# afron_atmega328_chassis_B.net
KiCad netlist of a schematic drawn in EAGLE
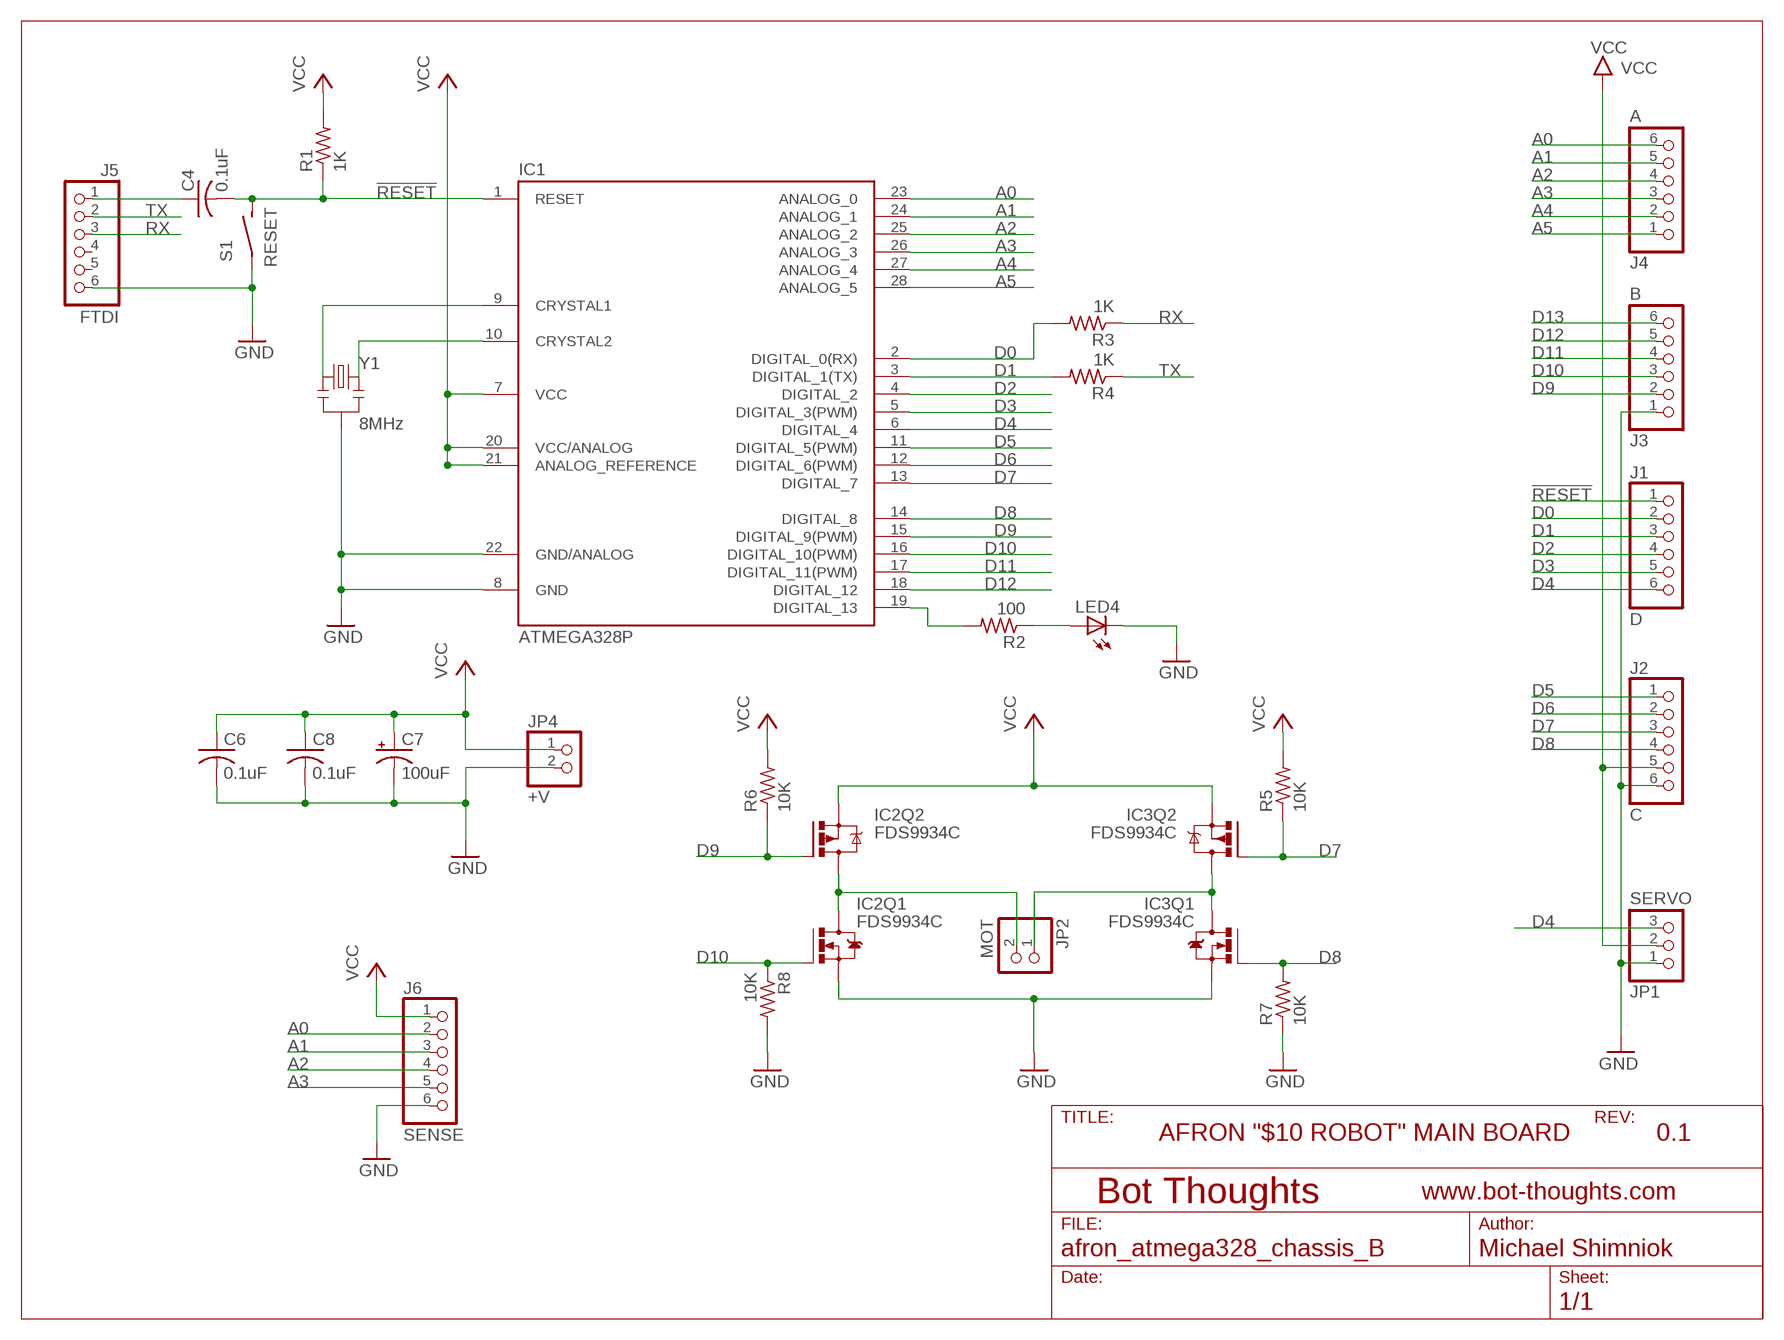
[diagram p0: schematic, sheet 1]

(export (version "E")
  (design (tool "Eeschema 10.0.6"))
  (components
    (comp (ref "C4")
      (value "0.1uF")
      (footprint "eagle-import:C050-024X044")
      (libsource (lib "eagle-import") (part "C-US050-024X044"))
    )
    (comp (ref "C6")
      (value "0.1uF")
      (footprint "eagle-import:C050-024X044")
      (libsource (lib "eagle-import") (part "C-US050-024X044"))
    )
    (comp (ref "C7")
      (value "100uF")
      (footprint "eagle-import:E2,5-6")
      (libsource (lib "eagle-import") (part "CPOL-USE2.5-6"))
    )
    (comp (ref "C8")
      (value "0.1uF")
      (footprint "eagle-import:C050-024X044")
      (libsource (lib "eagle-import") (part "C-US050-024X044"))
    )
    (comp (ref "IC1")
      (value "ATMEGA328P")
      (footprint "eagle-import:DIL28-3")
      (libsource (lib "eagle-import") (part "ATMEGA168-PU"))
    )
    (comp (ref "IC2")
      (value "FDS9934C")
      (footprint "eagle-import:SOIC8")
      (libsource (lib "eagle-import") (part "FDS9934C"))
    )
    (comp (ref "IC3")
      (value "FDS9934C")
      (footprint "eagle-import:SOIC8")
      (libsource (lib "eagle-import") (part "FDS9934C"))
    )
    (comp (ref "J1")
      (value "D")
      (footprint "eagle-import:1X06")
      (libsource (lib "eagle-import") (part "PINHD-1X06_2.54"))
    )
    (comp (ref "J2")
      (value "C")
      (footprint "eagle-import:1X06")
      (libsource (lib "eagle-import") (part "PINHD-1X06_2.54"))
    )
    (comp (ref "J3")
      (value "B")
      (footprint "eagle-import:1X06")
      (libsource (lib "eagle-import") (part "PINHD-1X06_2.54"))
    )
    (comp (ref "J4")
      (value "A")
      (footprint "eagle-import:1X06")
      (libsource (lib "eagle-import") (part "PINHD-1X06_2.54"))
    )
    (comp (ref "J5")
      (value "FTDI")
      (footprint "eagle-import:1X06")
      (libsource (lib "eagle-import") (part "PINHD-1X06_2.54"))
    )
    (comp (ref "J6")
      (value "SENSE")
      (footprint "eagle-import:1X06")
      (libsource (lib "eagle-import") (part "PINHD-1X06_2.54"))
    )
    (comp (ref "JP1")
      (value "SERVO")
      (footprint "eagle-import:1X03")
      (libsource (lib "eagle-import") (part "PINHD-1X03_2.54"))
    )
    (comp (ref "JP2")
      (value "MOT")
      (footprint "eagle-import:1X02-S")
      (libsource (lib "eagle-import") (part "PINHD-1X02_2.54-S"))
    )
    (comp (ref "JP4")
      (value "+V")
      (footprint "eagle-import:1X02-S")
      (libsource (lib "eagle-import") (part "PINHD-1X02_2.54-S"))
    )
    (comp (ref "LED4")
      (value "LED3MM")
      (footprint "eagle-import:LED3MM")
      (libsource (lib "eagle-import") (part "LED3MM"))
    )
    (comp (ref "R1")
      (value "1K")
      (footprint "eagle-import:0204_5")
      (libsource (lib "eagle-import") (part "R-US_0204/5"))
    )
    (comp (ref "R2")
      (value "100")
      (footprint "eagle-import:0204_5")
      (libsource (lib "eagle-import") (part "R-US_0204/5"))
    )
    (comp (ref "R3")
      (value "1K")
      (footprint "eagle-import:0204_5")
      (libsource (lib "eagle-import") (part "R-US_0204/5"))
    )
    (comp (ref "R4")
      (value "1K")
      (footprint "eagle-import:0204_5")
      (libsource (lib "eagle-import") (part "R-US_0204/5"))
    )
    (comp (ref "R5")
      (value "10K")
      (footprint "eagle-import:0204_5")
      (libsource (lib "eagle-import") (part "R-US_0204/5"))
    )
    (comp (ref "R6")
      (value "10K")
      (footprint "eagle-import:0204_5")
      (libsource (lib "eagle-import") (part "R-US_0204/5"))
    )
    (comp (ref "R7")
      (value "10K")
      (footprint "eagle-import:0204_5")
      (libsource (lib "eagle-import") (part "R-US_0204/5"))
    )
    (comp (ref "R8")
      (value "10K")
      (footprint "eagle-import:0204_5")
      (libsource (lib "eagle-import") (part "R-US_0204/5"))
    )
    (comp (ref "S1")
      (value "RESET")
      (footprint "eagle-import:6MMTACTILE")
      (libsource (lib "eagle-import") (part "SPST_TACT2"))
    )
    (comp (ref "Y1")
      (value "8MHz")
      (footprint "eagle-import:RESONATOR-PTH")
      (libsource (lib "eagle-import") (part "RESONATORPTH"))
    )
  )
  (nets
    (net (code "1") (name "/A0") (class "Default")
      (node (ref "IC1") (pin "23") (pinfunction "ANALOG_0_23") (pintype "bidirectional"))
      (node (ref "J4") (pin "6") (pinfunction "6_6") (pintype "passive"))
      (node (ref "J6") (pin "2") (pinfunction "2_2") (pintype "passive"))
    )
    (net (code "2") (name "/A1") (class "Default")
      (node (ref "IC1") (pin "24") (pinfunction "ANALOG_1_24") (pintype "bidirectional"))
      (node (ref "J4") (pin "5") (pinfunction "5_5") (pintype "passive"))
      (node (ref "J6") (pin "3") (pinfunction "3_3") (pintype "passive"))
    )
    (net (code "3") (name "/A2") (class "Default")
      (node (ref "IC1") (pin "25") (pinfunction "ANALOG_2_25") (pintype "bidirectional"))
      (node (ref "J4") (pin "4") (pinfunction "4_4") (pintype "passive"))
      (node (ref "J6") (pin "4") (pinfunction "4_4") (pintype "passive"))
    )
    (net (code "4") (name "/A3") (class "Default")
      (node (ref "IC1") (pin "26") (pinfunction "ANALOG_3_26") (pintype "bidirectional"))
      (node (ref "J4") (pin "3") (pinfunction "3_3") (pintype "passive"))
      (node (ref "J6") (pin "5") (pinfunction "5_5") (pintype "passive"))
    )
    (net (code "5") (name "/A4") (class "Default")
      (node (ref "IC1") (pin "27") (pinfunction "ANALOG_4_27") (pintype "bidirectional"))
      (node (ref "J4") (pin "2") (pinfunction "2_2") (pintype "passive"))
    )
    (net (code "6") (name "/A5") (class "Default")
      (node (ref "IC1") (pin "28") (pinfunction "ANALOG_5_28") (pintype "bidirectional"))
      (node (ref "J4") (pin "1") (pinfunction "1_1") (pintype "passive"))
    )
    (net (code "7") (name "/D0") (class "Default")
      (node (ref "IC1") (pin "2") (pinfunction "DIGITAL_0(RX)_2") (pintype "bidirectional"))
      (node (ref "J1") (pin "2") (pinfunction "2_2") (pintype "passive"))
      (node (ref "R3") (pin "2") (pinfunction "2_2") (pintype "passive"))
    )
    (net (code "8") (name "/D1") (class "Default")
      (node (ref "IC1") (pin "3") (pinfunction "DIGITAL_1(TX)_3") (pintype "bidirectional"))
      (node (ref "J1") (pin "3") (pinfunction "3_3") (pintype "passive"))
      (node (ref "R4") (pin "2") (pinfunction "2_2") (pintype "passive"))
    )
    (net (code "9") (name "/D2") (class "Default")
      (node (ref "IC1") (pin "4") (pinfunction "DIGITAL_2_4") (pintype "bidirectional"))
      (node (ref "J1") (pin "4") (pinfunction "4_4") (pintype "passive"))
    )
    (net (code "10") (name "/D3") (class "Default")
      (node (ref "IC1") (pin "5") (pinfunction "DIGITAL_3(PWM)_5") (pintype "bidirectional"))
      (node (ref "J1") (pin "5") (pinfunction "5_5") (pintype "passive"))
    )
    (net (code "11") (name "/D4") (class "Default")
      (node (ref "IC1") (pin "6") (pinfunction "DIGITAL_4_6") (pintype "bidirectional"))
      (node (ref "J1") (pin "6") (pinfunction "6_6") (pintype "passive"))
      (node (ref "JP1") (pin "3") (pinfunction "3_3") (pintype "passive"))
    )
    (net (code "12") (name "/D5") (class "Default")
      (node (ref "IC1") (pin "11") (pinfunction "DIGITAL_5(PWM)_11") (pintype "bidirectional"))
      (node (ref "J2") (pin "1") (pinfunction "1_1") (pintype "passive"))
    )
    (net (code "13") (name "/D6") (class "Default")
      (node (ref "IC1") (pin "12") (pinfunction "DIGITAL_6(PWM)_12") (pintype "bidirectional"))
      (node (ref "J2") (pin "2") (pinfunction "2_2") (pintype "passive"))
    )
    (net (code "14") (name "/D7") (class "Default")
      (node (ref "IC1") (pin "13") (pinfunction "DIGITAL_7_13") (pintype "bidirectional"))
      (node (ref "IC3") (pin "4") (pinfunction "G_4") (pintype "passive"))
      (node (ref "J2") (pin "3") (pinfunction "3_3") (pintype "passive"))
      (node (ref "R5") (pin "1") (pinfunction "1_1") (pintype "passive"))
    )
    (net (code "15") (name "/D8") (class "Default")
      (node (ref "IC1") (pin "14") (pinfunction "DIGITAL_8_14") (pintype "bidirectional"))
      (node (ref "IC3") (pin "2") (pinfunction "G_2") (pintype "passive"))
      (node (ref "J2") (pin "4") (pinfunction "4_4") (pintype "passive"))
      (node (ref "R7") (pin "2") (pinfunction "2_2") (pintype "passive"))
    )
    (net (code "16") (name "/D9") (class "Default")
      (node (ref "IC1") (pin "15") (pinfunction "DIGITAL_9(PWM)_15") (pintype "bidirectional"))
      (node (ref "IC2") (pin "4") (pinfunction "G_4") (pintype "passive"))
      (node (ref "J3") (pin "2") (pinfunction "2_2") (pintype "passive"))
      (node (ref "R6") (pin "1") (pinfunction "1_1") (pintype "passive"))
    )
    (net (code "17") (name "/D10") (class "Default")
      (node (ref "IC1") (pin "16") (pinfunction "DIGITAL_10(PWM)_16") (pintype "bidirectional"))
      (node (ref "IC2") (pin "2") (pinfunction "G_2") (pintype "passive"))
      (node (ref "J3") (pin "3") (pinfunction "3_3") (pintype "passive"))
      (node (ref "R8") (pin "1") (pinfunction "1_1") (pintype "passive"))
    )
    (net (code "18") (name "/D11") (class "Default")
      (node (ref "IC1") (pin "17") (pinfunction "DIGITAL_11(PWM)_17") (pintype "bidirectional"))
      (node (ref "J3") (pin "4") (pinfunction "4_4") (pintype "passive"))
    )
    (net (code "19") (name "/D12") (class "Default")
      (node (ref "IC1") (pin "18") (pinfunction "DIGITAL_12_18") (pintype "bidirectional"))
      (node (ref "J3") (pin "5") (pinfunction "5_5") (pintype "passive"))
    )
    (net (code "20") (name "/D13") (class "Default")
      (node (ref "IC1") (pin "19") (pinfunction "DIGITAL_13_19") (pintype "bidirectional"))
      (node (ref "J3") (pin "6") (pinfunction "6_6") (pintype "passive"))
      (node (ref "R2") (pin "2") (pinfunction "2_2") (pintype "passive"))
    )
    (net (code "21") (name "/RX") (class "Default")
      (node (ref "J5") (pin "3") (pinfunction "3_3") (pintype "passive"))
      (node (ref "R3") (pin "1") (pinfunction "1_1") (pintype "passive"))
    )
    (net (code "22") (name "/TX") (class "Default")
      (node (ref "J5") (pin "2") (pinfunction "2_2") (pintype "passive"))
      (node (ref "R4") (pin "1") (pinfunction "1_1") (pintype "passive"))
    )
    (net (code "23") (name "/~{RESET}") (class "Default")
      (node (ref "C4") (pin "2") (pinfunction "2_2") (pintype "passive"))
      (node (ref "IC1") (pin "1") (pinfunction "RESET_1") (pintype "bidirectional"))
      (node (ref "J1") (pin "1") (pinfunction "1_1") (pintype "passive"))
      (node (ref "R1") (pin "1") (pinfunction "1_1") (pintype "passive"))
      (node (ref "S1") (pin "P$2") (pinfunction "S_P$2") (pintype "passive"))
    )
    (net (code "24") (name "GND") (class "Default")
      (node (ref "C6") (pin "2") (pinfunction "2_2") (pintype "passive"))
      (node (ref "C7") (pin "-") (pinfunction "-_-") (pintype "passive"))
      (node (ref "C8") (pin "2") (pinfunction "2_2") (pintype "passive"))
      (node (ref "IC1") (pin "22") (pinfunction "GND/ANALOG_22") (pintype "power_in"))
      (node (ref "IC1") (pin "8") (pinfunction "GND_8") (pintype "power_in"))
      (node (ref "IC2") (pin "1") (pinfunction "S_1") (pintype "passive"))
      (node (ref "IC3") (pin "1") (pinfunction "S_1") (pintype "passive"))
      (node (ref "J2") (pin "6") (pinfunction "6_6") (pintype "passive"))
      (node (ref "J3") (pin "1") (pinfunction "1_1") (pintype "passive"))
      (node (ref "J5") (pin "6") (pinfunction "6_6") (pintype "passive"))
      (node (ref "J6") (pin "6") (pinfunction "6_6") (pintype "passive"))
      (node (ref "JP1") (pin "1") (pinfunction "1_1") (pintype "passive"))
      (node (ref "JP4") (pin "2") (pinfunction "2_2") (pintype "passive"))
      (node (ref "LED4") (pin "K") (pinfunction "C_K") (pintype "passive"))
      (node (ref "R7") (pin "1") (pinfunction "1_1") (pintype "passive"))
      (node (ref "R8") (pin "2") (pinfunction "2_2") (pintype "passive"))
      (node (ref "S1") (pin "P$1") (pinfunction "P_P$1") (pintype "passive"))
      (node (ref "Y1") (pin "2") (pinfunction "2_2") (pintype "passive"))
    )
    (net (code "25") (name "Net-(C4-Pad1)") (class "Default")
      (node (ref "C4") (pin "1") (pinfunction "1_1") (pintype "passive"))
      (node (ref "J5") (pin "1") (pinfunction "1_1") (pintype "passive"))
    )
    (net (code "26") (name "Net-(IC1-CRYSTAL1)") (class "Default")
      (node (ref "IC1") (pin "9") (pinfunction "CRYSTAL1_9") (pintype "bidirectional"))
      (node (ref "Y1") (pin "1") (pinfunction "1_1") (pintype "passive"))
    )
    (net (code "27") (name "Net-(IC1-CRYSTAL2)") (class "Default")
      (node (ref "IC1") (pin "10") (pinfunction "CRYSTAL2_10") (pintype "bidirectional"))
      (node (ref "Y1") (pin "3") (pinfunction "3_3") (pintype "passive"))
    )
    (net (code "28") (name "Net-(IC2A-D-Pad7)") (class "Default")
      (node (ref "IC2") (pin "5") (pinfunction "D_5") (pintype "passive"))
      (node (ref "IC2") (pin "6") (pinfunction "D_6") (pintype "passive"))
      (node (ref "IC2") (pin "7") (pinfunction "D_7") (pintype "passive"))
      (node (ref "IC2") (pin "8") (pinfunction "D_8") (pintype "passive"))
      (node (ref "JP2") (pin "2") (pinfunction "2_2") (pintype "passive"))
    )
    (net (code "29") (name "Net-(IC3A-D-Pad7)") (class "Default")
      (node (ref "IC3") (pin "5") (pinfunction "D_5") (pintype "passive"))
      (node (ref "IC3") (pin "6") (pinfunction "D_6") (pintype "passive"))
      (node (ref "IC3") (pin "7") (pinfunction "D_7") (pintype "passive"))
      (node (ref "IC3") (pin "8") (pinfunction "D_8") (pintype "passive"))
      (node (ref "JP2") (pin "1") (pinfunction "1_1") (pintype "passive"))
    )
    (net (code "30") (name "Net-(LED4-PadA)") (class "Default")
      (node (ref "LED4") (pin "A") (pinfunction "A_A") (pintype "passive"))
      (node (ref "R2") (pin "1") (pinfunction "1_1") (pintype "passive"))
    )
    (net (code "31") (name "VCC") (class "Default")
      (node (ref "C6") (pin "1") (pinfunction "1_1") (pintype "passive"))
      (node (ref "C7") (pin "+") (pinfunction "+_+") (pintype "passive"))
      (node (ref "C8") (pin "1") (pinfunction "1_1") (pintype "passive"))
      (node (ref "IC1") (pin "20") (pinfunction "VCC/ANALOG_20") (pintype "passive"))
      (node (ref "IC1") (pin "21") (pinfunction "ANALOG_REFERENCE_21") (pintype "passive"))
      (node (ref "IC1") (pin "7") (pinfunction "VCC_7") (pintype "power_in"))
      (node (ref "IC2") (pin "3") (pinfunction "S_3") (pintype "passive"))
      (node (ref "IC3") (pin "3") (pinfunction "S_3") (pintype "passive"))
      (node (ref "J2") (pin "5") (pinfunction "5_5") (pintype "passive"))
      (node (ref "J6") (pin "1") (pinfunction "1_1") (pintype "passive"))
      (node (ref "JP1") (pin "2") (pinfunction "2_2") (pintype "passive"))
      (node (ref "JP4") (pin "1") (pinfunction "1_1") (pintype "passive"))
      (node (ref "R1") (pin "2") (pinfunction "2_2") (pintype "passive"))
      (node (ref "R5") (pin "2") (pinfunction "2_2") (pintype "passive"))
      (node (ref "R6") (pin "2") (pinfunction "2_2") (pintype "passive"))
    )
    (net (code "32") (name "unconnected-(J5-Pad4)") (class "Default")
      (node (ref "J5") (pin "4") (pinfunction "4_4") (pintype "passive"))
    )
    (net (code "33") (name "unconnected-(J5-Pad5)") (class "Default")
      (node (ref "J5") (pin "5") (pinfunction "5_5") (pintype "passive"))
    )
  )
)
